# PSFB_bus_sense.net
KiCad netlist of a schematic drawn in Altium Designer
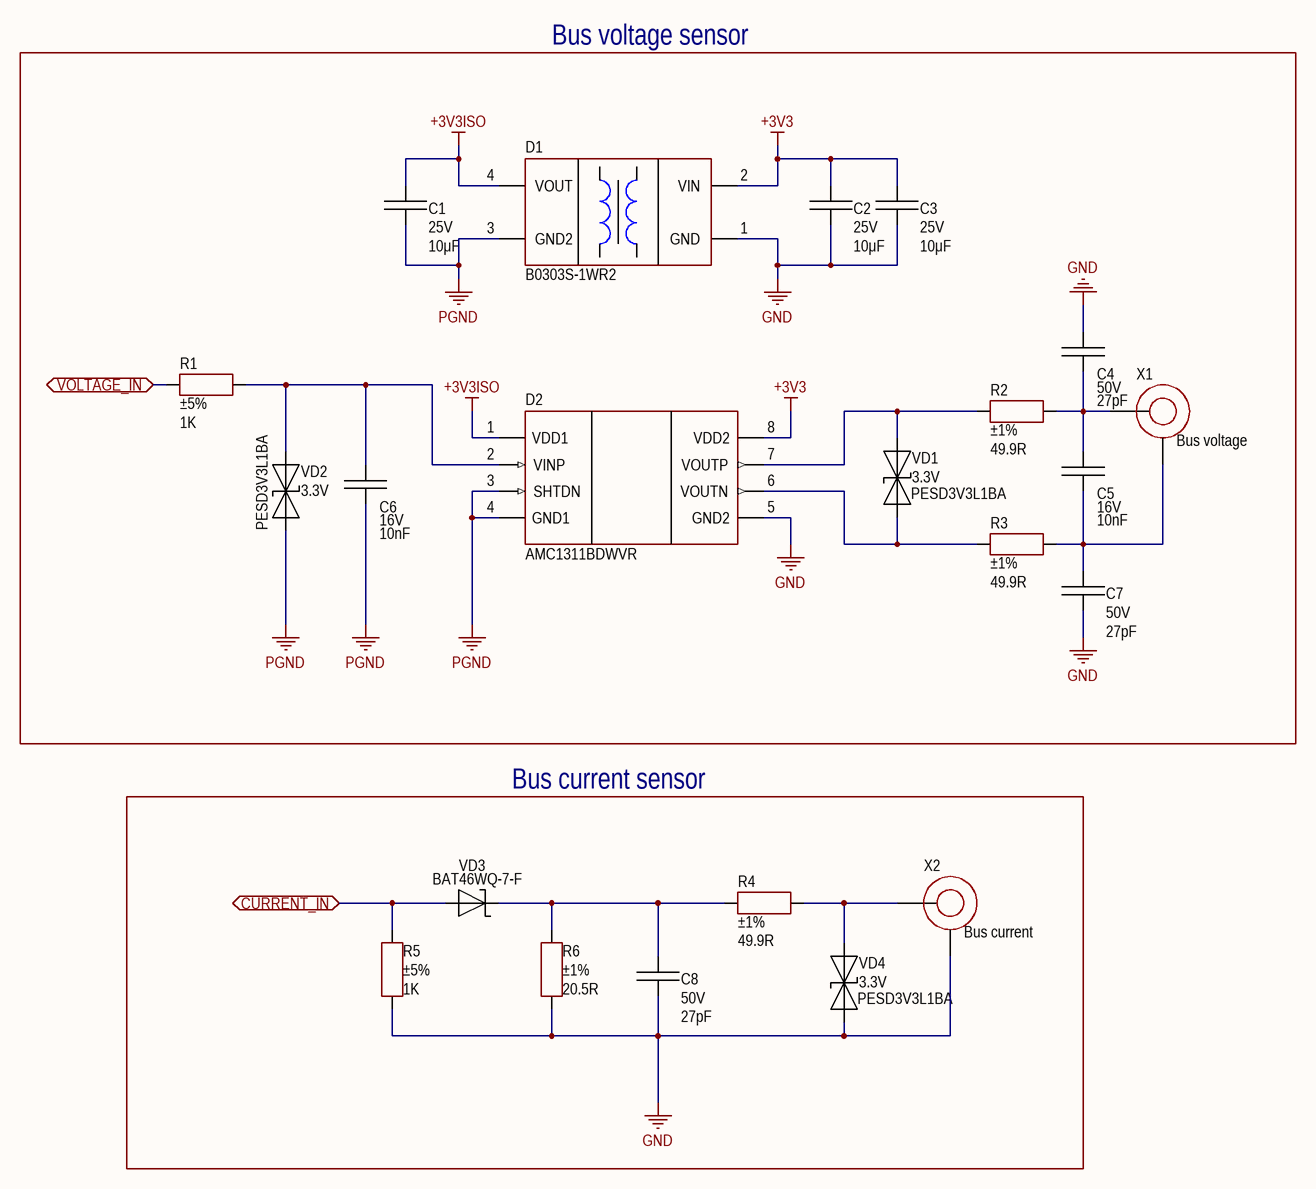
[diagram p0: PSFB_bus_sense.SchDoc]

(export (version "E")
  (design (tool "Eeschema 10.0.6"))
  (components
    (comp (ref "C1")
      (value "10μF")
      (footprint "CAP: 1206")
      (description "10µF ±10% 25V Ceramic Capacitor X7R 1206 (3216 Metric)")
      (fields
        (field (name "MANUFACTURER") "Yageo")
        (field (name "PARTNUMBER") "CC1206KKX7R8BB106")
        (field (name "VOLTAGE") "25V")
      )
      (libsource (lib "capacitor") (part "Ceramic_1206"))
    )
    (comp (ref "C2")
      (value "10μF")
      (footprint "CAP: 1206")
      (description "10µF ±10% 25V Ceramic Capacitor X7R 1206 (3216 Metric)")
      (fields
        (field (name "MANUFACTURER") "Yageo")
        (field (name "PARTNUMBER") "CC1206KKX7R8BB106")
        (field (name "VOLTAGE") "25V")
      )
      (libsource (lib "capacitor") (part "Ceramic_1206"))
    )
    (comp (ref "C3")
      (value "10μF")
      (footprint "CAP: 1206")
      (description "10µF ±10% 25V Ceramic Capacitor X7R 1206 (3216 Metric)")
      (fields
        (field (name "MANUFACTURER") "Yageo")
        (field (name "PARTNUMBER") "CC1206KKX7R8BB106")
        (field (name "VOLTAGE") "25V")
      )
      (libsource (lib "capacitor") (part "Ceramic_1206"))
    )
    (comp (ref "C4")
      (value "27pF")
      (footprint "CAP: 0805")
      (description "27pF ±5% 50V Ceramic Capacitor C0G, NP0 0805 (2012 Metric)")
      (fields
        (field (name "MANUFACTURER") "Yageo")
        (field (name "PARTNUMBER") "CC0805JRNPO9BN270")
        (field (name "VOLTAGE") "50V")
      )
      (libsource (lib "capacitor") (part "Ceramic_0805"))
    )
    (comp (ref "C5")
      (value "10nF")
      (footprint "CAP: 0805")
      (description "27pF ±5% 50V Ceramic Capacitor C0G, NP0 0805 (2012 Metric)")
      (fields
        (field (name "MANUFACTURER") "Yageo")
        (field (name "PARTNUMBER") "CC0805JKNPO7BN103")
        (field (name "VOLTAGE") "16V")
      )
      (libsource (lib "capacitor") (part "Ceramic_0805"))
    )
    (comp (ref "C6")
      (value "10nF")
      (footprint "CAP: 0805")
      (description "27pF ±5% 50V Ceramic Capacitor C0G, NP0 0805 (2012 Metric)")
      (fields
        (field (name "MANUFACTURER") "Yageo")
        (field (name "PARTNUMBER") "CC0805JKNPO7BN103")
        (field (name "VOLTAGE") "16V")
      )
      (libsource (lib "capacitor") (part "Ceramic_0805"))
    )
    (comp (ref "C7")
      (value "27pF")
      (footprint "CAP: 0805")
      (description "27pF ±5% 50V Ceramic Capacitor C0G, NP0 0805 (2012 Metric)")
      (fields
        (field (name "MANUFACTURER") "Yageo")
        (field (name "PARTNUMBER") "CC0805JRNPO9BN270")
        (field (name "VOLTAGE") "50V")
      )
      (libsource (lib "capacitor") (part "Ceramic_0805"))
    )
    (comp (ref "C8")
      (value "27pF")
      (footprint "CAP: 0805")
      (description "27pF ±5% 50V Ceramic Capacitor C0G, NP0 0805 (2012 Metric)")
      (fields
        (field (name "MANUFACTURER") "Yageo")
        (field (name "PARTNUMBER") "CC0805JRNPO9BN270")
        (field (name "VOLTAGE") "50V")
      )
      (libsource (lib "capacitor") (part "Ceramic_0805"))
    )
    (comp (ref "D1")
      (value "~")
      (footprint "MOD: SIP-4 (B0505S-1W)")
      (description "Isolated Module DC DC Converter 1 Output 3.3V 303mA 2.97V - 3.63V Input")
      (fields
        (field (name "MANUFACTURER") "Mornsun")
        (field (name "VALUEMANUFACTURERPARTNUMBER") "DC/DC converter, isolator, 5V 200mA, -40...+105°C, SIP-4")
        (field (name "PARTNUMBER") "B0303S-1WR2")
      )
      (libsource (lib "module") (part "B0505S-1WR2"))
    )
    (comp (ref "D2")
      (value "~")
      (footprint "8-SOIC-W")
      (description "Isolator amplifier")
      (fields
        (field (name "MANUFACTURER") "Texas Instruments")
        (field (name "VALUEMANUFACTURERPARTNUMBER") "IC isolator amplifier, Differential, 220 kHz, 2.7...5.5V, -40...+105°C, 8-SOIC")
        (field (name "PARTNUMBER") "AMC1311BDWVR")
      )
      (libsource (lib "MyLib") (part "AMC1200BDWVR"))
    )
    (comp (ref "R1")
      (value "1K")
      (footprint "RES: 0805")
      (description "1 kOhms ±5% 0.125W, 1/8W Chip Resistor 0805 (2012 Metric) Moisture Resistant Thick Film")
      (fields
        (field (name "MANUFACTURER") "Yageo")
        (field (name "PARTNUMBER") "RC0805JR-071KL")
        (field (name "TOLERANCE") "±5%")
      )
      (libsource (lib "resistor") (part "Resistor_0805"))
    )
    (comp (ref "R2")
      (value "49.9R")
      (footprint "RES: 0805")
      (description "49.9 Ohms ±1% 0.125W, 1/8W Chip Resistor 0805 (2012 Metric) Moisture Resistant Thick Film")
      (fields
        (field (name "MANUFACTURER") "Yageo")
        (field (name "PARTNUMBER") "RC0805FR-0749R9L")
        (field (name "TOLERANCE") "±1%")
      )
      (libsource (lib "") (part "Resistor_0805_1"))
    )
    (comp (ref "R3")
      (value "49.9R")
      (footprint "RES: 0805")
      (description "49.9 Ohms ±1% 0.125W, 1/8W Chip Resistor 0805 (2012 Metric) Moisture Resistant Thick Film")
      (fields
        (field (name "MANUFACTURER") "Yageo")
        (field (name "PARTNUMBER") "RC0805FR-0749R9L")
        (field (name "TOLERANCE") "±1%")
      )
      (libsource (lib "") (part "Resistor_0805_1"))
    )
    (comp (ref "R4")
      (value "49.9R")
      (footprint "RES: 0805")
      (description "49.9 Ohms ±1% 0.125W, 1/8W Chip Resistor 0805 (2012 Metric) Moisture Resistant Thick Film")
      (fields
        (field (name "MANUFACTURER") "Yageo")
        (field (name "PARTNUMBER") "RC0805FR-0749R9L")
        (field (name "TOLERANCE") "±1%")
      )
      (libsource (lib "") (part "Resistor_0805_1"))
    )
    (comp (ref "R5")
      (value "1K")
      (footprint "RES: 0805")
      (description "1 kOhms ±5% 0.125W, 1/8W Chip Resistor 0805 (2012 Metric) Moisture Resistant Thick Film")
      (fields
        (field (name "MANUFACTURER") "Yageo")
        (field (name "PARTNUMBER") "RC0805JR-071KL")
        (field (name "TOLERANCE") "±5%")
      )
      (libsource (lib "") (part "Resistor_0805_2"))
    )
    (comp (ref "R6")
      (value "20.5R")
      (footprint "RES: 2512")
      (description "20.5 Ohms ±1% 1W Chip Resistor 2512 (6432 Metric) Moisture Resistant Thick Film")
      (fields
        (field (name "MANUFACTURER") "Yageo")
        (field (name "PARTNUMBER") "RC2512FK-0720R5L")
        (field (name "TOLERANCE") "±1%")
      )
      (libsource (lib "resistor") (part "Resistor_2512"))
    )
    (comp (ref "VD1")
      (value "~")
      (footprint "DIODE: SOD323")
      (description "3.3V Reverse Standoff 26V Clamp 18A (8/20µs) Ipp Tvs Diode Surface Mount SOD-323")
      (fields
        (field (name "MANUFACTURER") "Diodes Incorporated")
        (field (name "VALUEMANUFACTURERPARTNUMBER") "TVS diode, 3.3V, 500W, , , SOD-323, -55...+150°C")
        (field (name "VOLTAGE") "3.3V")
        (field (name "PARTNUMBER") "PESD3V3L1BA")
      )
      (libsource (lib "diode") (part "TVS_single"))
    )
    (comp (ref "VD2")
      (value "~")
      (footprint "DIODE: SOD323")
      (description "3.3V Reverse Standoff 26V Clamp 18A (8/20µs) Ipp Tvs Diode Surface Mount SOD-323")
      (fields
        (field (name "MANUFACTURER") "Diodes Incorporated")
        (field (name "VALUEMANUFACTURERPARTNUMBER") "TVS diode, 3.3V, 500W, , , SOD-323, -55...+150°C")
        (field (name "VOLTAGE") "3.3V")
        (field (name "PARTNUMBER") "PESD3V3L1BA")
      )
      (libsource (lib "diode") (part "TVS_single"))
    )
    (comp (ref "VD3")
      (value "~")
      (footprint "DIODE: SOD123")
      (description "Diode Schottky 100V 150mA Surface Mount SOD-123")
      (fields
        (field (name "MANUFACTURER") "Diodes Incorporated")
        (field (name "VALUEMANUFACTURERPARTNUMBER") "Schottky diode, 100V, 1A, 0.45V, 15pF, SOD-123, -55...+150°C")
        (field (name "PARTNUMBER") "BAT46WQ-7-F")
      )
      (libsource (lib "diode") (part "Schottky_single"))
    )
    (comp (ref "VD4")
      (value "~")
      (footprint "DIODE: SOD323")
      (description "3.3V Reverse Standoff 26V Clamp 18A (8/20µs) Ipp Tvs Diode Surface Mount SOD-323")
      (fields
        (field (name "MANUFACTURER") "Diodes Incorporated")
        (field (name "VALUEMANUFACTURERPARTNUMBER") "TVS diode, 3.3V, 500W, , , SOD-323, -55...+150°C")
        (field (name "VOLTAGE") "3.3V")
        (field (name "PARTNUMBER") "PESD3V3L1BA")
      )
      (libsource (lib "diode") (part "TVS_single"))
    )
    (comp (ref "X1")
      (value "~")
      (footprint "60311002111526")
      (description "SMA Connector Jack, Female Socket 50Ohm Through Hole Solder")
      (fields
        (field (name "MANUFACTURER") "Würth Elektronik")
        (field (name "VALUEMANUFACTURERPARTNUMBER") "Connector SMA, 50 Ohm, 6Hz")
        (field (name "COMMENTTEXT") "Bus voltage")
      )
      (libsource (lib "connector") (part "Connector_SMA"))
    )
    (comp (ref "X2")
      (value "~")
      (footprint "60311002111526")
      (description "SMA Connector Jack, Female Socket 50Ohm Through Hole Solder")
      (fields
        (field (name "MANUFACTURER") "Würth Elektronik")
        (field (name "VALUEMANUFACTURERPARTNUMBER") "Connector SMA, 50 Ohm, 6Hz")
        (field (name "COMMENTTEXT") "Bus current")
      )
      (libsource (lib "connector") (part "Connector_SMA"))
    )
  )
  (nets
    (net (code "1") (name "+3V3") (class "Default")
      (node (ref "C2") (pin "2") (pinfunction "2_2") (pintype "passive"))
      (node (ref "C3") (pin "2") (pinfunction "2_2") (pintype "passive"))
      (node (ref "D1") (pin "2") (pinfunction "VIN_2") (pintype "power_in"))
      (node (ref "D2") (pin "8") (pinfunction "VDD2_8") (pintype "power_in"))
    )
    (net (code "2") (name "+3V3ISO") (class "Default")
      (node (ref "C1") (pin "2") (pinfunction "2_2") (pintype "passive"))
      (node (ref "D1") (pin "4") (pinfunction "VOUT_4") (pintype "power_in"))
      (node (ref "D2") (pin "1") (pinfunction "VDD1_1") (pintype "power_in"))
    )
    (net (code "3") (name "/CURRENT_IN") (class "Default")
      (node (ref "R5") (pin "2") (pinfunction "2_2") (pintype "passive"))
      (node (ref "VD3") (pin "1") (pinfunction "1_1") (pintype "passive"))
    )
    (net (code "4") (name "/VOLTAGE_IN") (class "Default")
      (node (ref "R1") (pin "2") (pinfunction "2_2") (pintype "passive"))
    )
    (net (code "5") (name "GND") (class "Default")
      (node (ref "C2") (pin "1") (pinfunction "1_1") (pintype "passive"))
      (node (ref "C3") (pin "1") (pinfunction "1_1") (pintype "passive"))
      (node (ref "C4") (pin "2") (pinfunction "2_2") (pintype "passive"))
      (node (ref "C7") (pin "2") (pinfunction "2_2") (pintype "passive"))
      (node (ref "C8") (pin "2") (pinfunction "2_2") (pintype "passive"))
      (node (ref "D1") (pin "1") (pinfunction "GND_1") (pintype "power_in"))
      (node (ref "D2") (pin "5") (pinfunction "GND2_5") (pintype "power_in"))
      (node (ref "R5") (pin "1") (pinfunction "1_1") (pintype "passive"))
      (node (ref "R6") (pin "1") (pinfunction "1_1") (pintype "passive"))
      (node (ref "VD4") (pin "1") (pinfunction "A_1") (pintype "passive"))
      (node (ref "X2") (pin "2") (pinfunction "2_2") (pintype "passive"))
    )
    (net (code "6") (name "Net-(C4-Pad1)") (class "Default")
      (node (ref "C4") (pin "1") (pinfunction "1_1") (pintype "passive"))
      (node (ref "C5") (pin "2") (pinfunction "2_2") (pintype "passive"))
      (node (ref "R2") (pin "1") (pinfunction "1_1") (pintype "passive"))
      (node (ref "X1") (pin "1") (pinfunction "1_1") (pintype "passive"))
    )
    (net (code "7") (name "Net-(C5-Pad1)") (class "Default")
      (node (ref "C5") (pin "1") (pinfunction "1_1") (pintype "passive"))
      (node (ref "C7") (pin "1") (pinfunction "1_1") (pintype "passive"))
      (node (ref "R3") (pin "1") (pinfunction "1_1") (pintype "passive"))
      (node (ref "X1") (pin "2") (pinfunction "2_2") (pintype "passive"))
    )
    (net (code "8") (name "Net-(C8-Pad1)") (class "Default")
      (node (ref "C8") (pin "1") (pinfunction "1_1") (pintype "passive"))
      (node (ref "R4") (pin "2") (pinfunction "2_2") (pintype "passive"))
      (node (ref "R6") (pin "2") (pinfunction "2_2") (pintype "passive"))
      (node (ref "VD3") (pin "2") (pinfunction "2_2") (pintype "passive"))
    )
    (net (code "9") (name "Net-(D2-VINP)") (class "Default")
      (node (ref "C6") (pin "2") (pinfunction "2_2") (pintype "passive"))
      (node (ref "D2") (pin "2") (pinfunction "VINP_2") (pintype "input"))
      (node (ref "R1") (pin "1") (pinfunction "1_1") (pintype "passive"))
      (node (ref "VD2") (pin "2") (pinfunction "C_2") (pintype "passive"))
    )
    (net (code "10") (name "Net-(D2-VOUTN)") (class "Default")
      (node (ref "D2") (pin "6") (pinfunction "VOUTN_6") (pintype "output"))
      (node (ref "R3") (pin "2") (pinfunction "2_2") (pintype "passive"))
      (node (ref "VD1") (pin "1") (pinfunction "A_1") (pintype "passive"))
    )
    (net (code "11") (name "Net-(D2-VOUTP)") (class "Default")
      (node (ref "D2") (pin "7") (pinfunction "VOUTP_7") (pintype "output"))
      (node (ref "R2") (pin "2") (pinfunction "2_2") (pintype "passive"))
      (node (ref "VD1") (pin "2") (pinfunction "C_2") (pintype "passive"))
    )
    (net (code "12") (name "Net-(VD4-C)") (class "Default")
      (node (ref "R4") (pin "1") (pinfunction "1_1") (pintype "passive"))
      (node (ref "VD4") (pin "2") (pinfunction "C_2") (pintype "passive"))
      (node (ref "X2") (pin "1") (pinfunction "1_1") (pintype "passive"))
    )
    (net (code "13") (name "PGND") (class "Default")
      (node (ref "C1") (pin "1") (pinfunction "1_1") (pintype "passive"))
      (node (ref "C6") (pin "1") (pinfunction "1_1") (pintype "passive"))
      (node (ref "D1") (pin "3") (pinfunction "GND2_3") (pintype "power_in"))
      (node (ref "D2") (pin "3") (pinfunction "SHTDN_3") (pintype "input"))
      (node (ref "D2") (pin "4") (pinfunction "GND1_4") (pintype "power_in"))
      (node (ref "VD2") (pin "1") (pinfunction "A_1") (pintype "passive"))
    )
  )
)
